# 3_LTE_2.net
KiCad netlist of a schematic drawn in Altium Designer
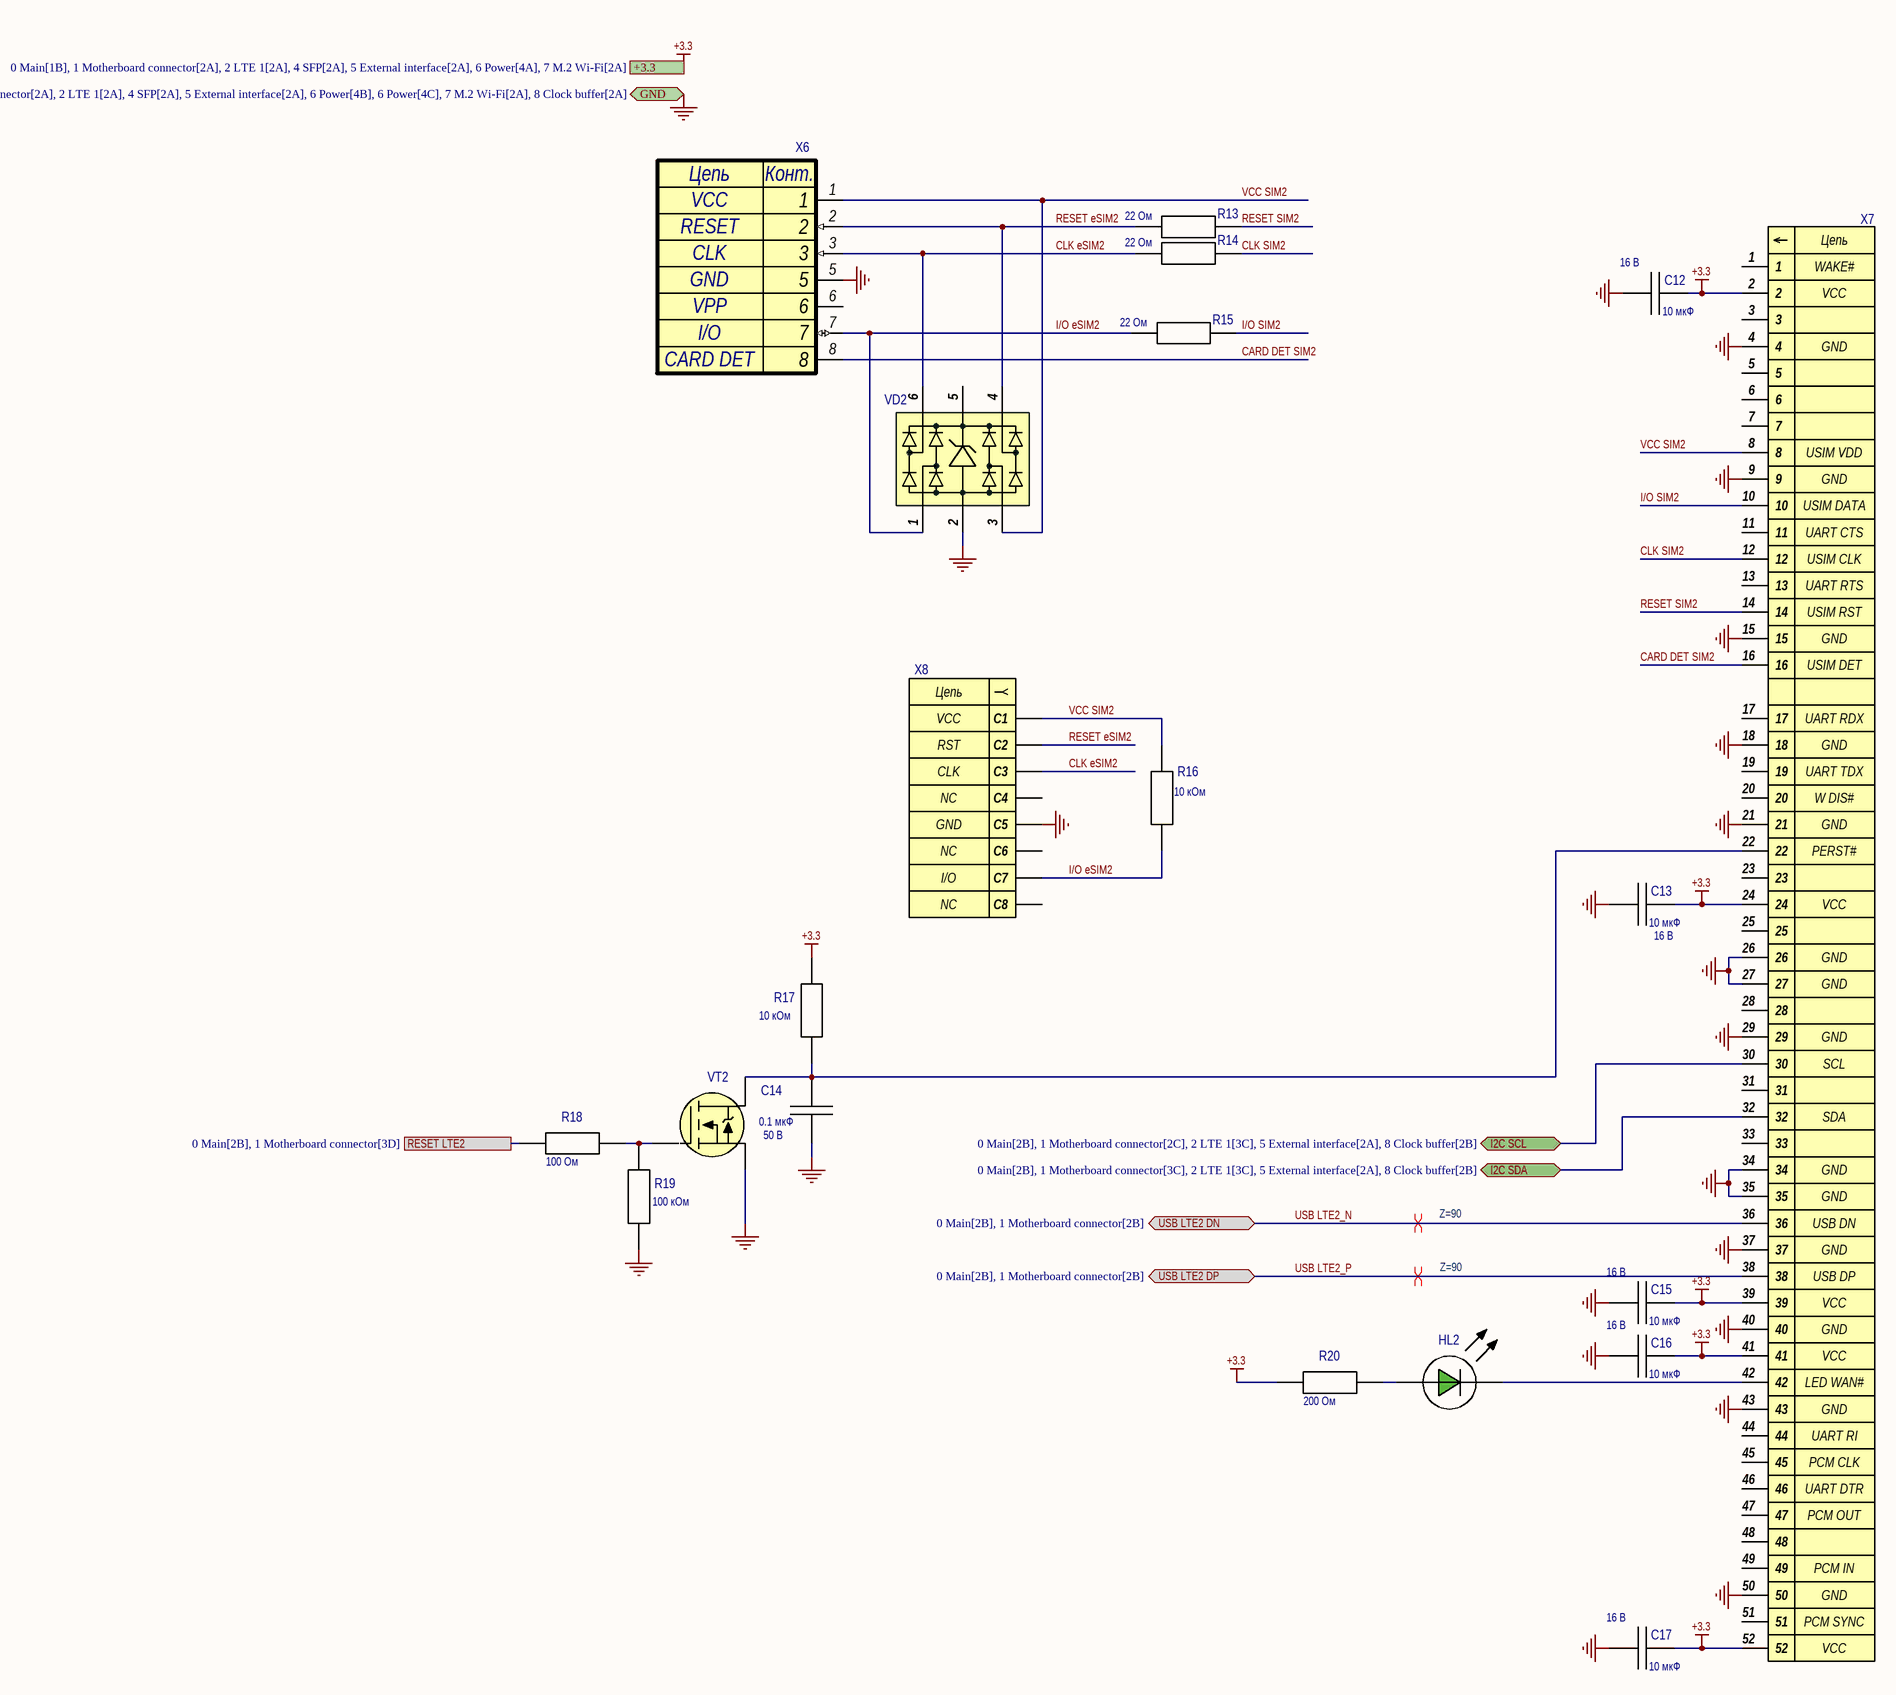
[diagram p0: 3 LTE 2.SchDoc]

(export (version "E")
  (design (tool "Eeschema 10.0.6"))
  (components
    (comp (ref "C12")
      (value "10 мкФ")
      (footprint "CAP_0805")
      (description "Конденсатор CHIP-0805 10 мкФ 16 В 10% X5R")
      (fields
        (field (name "PARTNUMBER") "GRM21BR61C106KE15L")
        (field (name "TOLERANCE") "10%")
        (field (name "НАПРЯЖЕНИЕ") "16 В")
        (field (name "AUTOR") "Цислав А.Н.")
      )
      (libsource (lib "Database_Altium") (part "STD_CAP"))
    )
    (comp (ref "C13")
      (value "10 мкФ")
      (footprint "CAP_0805")
      (description "Конденсатор CHIP-0805 10 мкФ 16 В 10% X5R")
      (fields
        (field (name "PARTNUMBER") "GRM21BR61C106KE15L")
        (field (name "TOLERANCE") "10%")
        (field (name "НАПРЯЖЕНИЕ") "16 В")
        (field (name "AUTOR") "Цислав А.Н.")
      )
      (libsource (lib "Database_Altium") (part "STD_CAP"))
    )
    (comp (ref "C14")
      (value "0.1 мкФ")
      (footprint "CAP_0402")
      (description "Конденсатор CHIP-0402 0.1 мкФ 50 В 10% X7R")
      (fields
        (field (name "PARTNUMBER") "CC0402KRX7R9BB104")
        (field (name "TOLERANCE") "10%")
        (field (name "НАПРЯЖЕНИЕ") "50 В")
        (field (name "AUTOR") "Admin")
      )
      (libsource (lib "Database_Altium") (part "STD_CAP"))
    )
    (comp (ref "C15")
      (value "10 мкФ")
      (footprint "CAP_0805")
      (description "Конденсатор CHIP-0805 10 мкФ 16 В 10% X5R")
      (fields
        (field (name "PARTNUMBER") "GRM21BR61C106KE15L")
        (field (name "TOLERANCE") "10%")
        (field (name "НАПРЯЖЕНИЕ") "16 В")
        (field (name "AUTOR") "Цислав А.Н.")
      )
      (libsource (lib "Database_Altium") (part "STD_CAP"))
    )
    (comp (ref "C16")
      (value "10 мкФ")
      (footprint "CAP_0805")
      (description "Конденсатор CHIP-0805 10 мкФ 16 В 10% X5R")
      (fields
        (field (name "PARTNUMBER") "GRM21BR61C106KE15L")
        (field (name "TOLERANCE") "10%")
        (field (name "НАПРЯЖЕНИЕ") "16 В")
        (field (name "AUTOR") "Цислав А.Н.")
      )
      (libsource (lib "Database_Altium") (part "STD_CAP"))
    )
    (comp (ref "C17")
      (value "10 мкФ")
      (footprint "CAP_0805")
      (description "Конденсатор CHIP-0805 10 мкФ 16 В 10% X5R")
      (fields
        (field (name "PARTNUMBER") "GRM21BR61C106KE15L")
        (field (name "TOLERANCE") "10%")
        (field (name "НАПРЯЖЕНИЕ") "16 В")
        (field (name "AUTOR") "Цислав А.Н.")
      )
      (libsource (lib "Database_Altium") (part "STD_CAP"))
    )
    (comp (ref "HL2")
      (value "APHHS1005CGCK")
      (footprint "LED_0402_GREEN")
      (description "Диод Kingbright 2 В 20 мА")
      (fields (field (name "MANUFACTURER") "Kingbright") (field (name "AUTOR") "Цислав А.Н."))
      (libsource (lib "Database_Altium") (part "APHHS1005CGCK"))
    )
    (comp (ref "R13")
      (value "22 Ом")
      (footprint "RES_0402")
      (description "Резистор CHIP-0402 22 Ом 1%")
      (fields
        (field (name "PARTNUMBER") "RC0402FR-0722RL")
        (field (name "TOLERANCE") "1%")
        (field (name "AUTOR") "Цислав А.Н.")
      )
      (libsource (lib "Database_Altium") (part "STD_RES"))
    )
    (comp (ref "R14")
      (value "22 Ом")
      (footprint "RES_0402")
      (description "Резистор CHIP-0402 22 Ом 1%")
      (fields
        (field (name "PARTNUMBER") "RC0402FR-0722RL")
        (field (name "TOLERANCE") "1%")
        (field (name "AUTOR") "Цислав А.Н.")
      )
      (libsource (lib "Database_Altium") (part "STD_RES"))
    )
    (comp (ref "R15")
      (value "22 Ом")
      (footprint "RES_0402")
      (description "Резистор CHIP-0402 22 Ом 1%")
      (fields
        (field (name "PARTNUMBER") "RC0402FR-0722RL")
        (field (name "TOLERANCE") "1%")
        (field (name "AUTOR") "Цислав А.Н.")
      )
      (libsource (lib "Database_Altium") (part "STD_RES"))
    )
    (comp (ref "R16")
      (value "10 кОм")
      (footprint "RES_0402")
      (description "Резистор CHIP-0402 10 кОм 5%")
      (fields
        (field (name "PARTNUMBER") "RC0402JR-0710KL")
        (field (name "TOLERANCE") "5%")
        (field (name "AUTOR") "Цислав А.Н.")
      )
      (libsource (lib "Database_Altium") (part "STD_RES"))
    )
    (comp (ref "R17")
      (value "10 кОм")
      (footprint "RES_0402")
      (description "Резистор CHIP-0402 10 кОм 5%")
      (fields
        (field (name "PARTNUMBER") "RC0402JR-0710KL")
        (field (name "TOLERANCE") "5%")
        (field (name "AUTOR") "Цислав А.Н.")
      )
      (libsource (lib "Database_Altium") (part "STD_RES"))
    )
    (comp (ref "R18")
      (value "100 Ом")
      (footprint "RES_0402")
      (description "Резистор CHIP-0402 100 Ом 5%")
      (fields
        (field (name "PARTNUMBER") "RC0402JR-07100RL")
        (field (name "TOLERANCE") "5%")
        (field (name "AUTOR") "Цислав А.Н.")
      )
      (libsource (lib "Database_Altium") (part "STD_RES"))
    )
    (comp (ref "R19")
      (value "100 кОм")
      (footprint "RES_0402")
      (description "Резистор CHIP-0402 100 кОм 5%")
      (fields
        (field (name "PARTNUMBER") "RC0402JR-07100KL")
        (field (name "TOLERANCE") "5%")
        (field (name "AUTOR") "Цислав А.Н.")
      )
      (libsource (lib "Database_Altium") (part "STD_RES"))
    )
    (comp (ref "R20")
      (value "200 Ом")
      (footprint "RES_0402")
      (description "Резистор CHIP-0402 200 Ом 5%")
      (fields
        (field (name "PARTNUMBER") "RC0402JR-07200RL")
        (field (name "TOLERANCE") "5%")
        (field (name "AUTOR") "Цислав А.Н.")
      )
      (libsource (lib "Database_Altium") (part "STD_RES"))
    )
    (comp (ref "VD2")
      (value "SRV05-4")
      (footprint "SOT-23-6")
      (description "Диод SEMTECH 1.2 В 12 А")
      (fields (field (name "MANUFACTURER") "SEMTECH") (field (name "AUTOR") "Admin"))
      (libsource (lib "Database_Altium") (part "SRV05-4"))
    )
    (comp (ref "VT2")
      (value "2N7002P")
      (footprint "SOT-23-3")
      (description "Микросхема NXP  N-channel Trench MOSFET")
      (fields
        (field (name "VOLTAGE") "60В")
        (field (name "MANUFACTURER") "NXP")
        (field (name "AUTOR") "Admin")
      )
      (libsource (lib "Database_Altium") (part "2N7002P"))
    )
    (comp (ref "X6")
      (value "Sim холдер с детектированием sim-card  и выдвижным держателем SMN-327-KT1B")
      (footprint "SMN-328-ACP7")
      (description "Разъем XunPu SIM")
      (fields
        (field (name "PARTNUMBER") "SMN-328-ACP7")
        (field (name "MANUFACTURER") "XunPu")
        (field (name "CONTACT") "8")
        (field (name "AUTOR") "Admin")
      )
      (libsource (lib "Database_Altium") (part "Sim WITH CD"))
    )
    (comp (ref "X7")
      (value "2041262-1")
      (footprint "2041262-1")
      (description "Разъем TE PCI-E")
      (fields (field (name "MANUFACTURER") "TE") (field (name "CONTACT") "52") (field (name "AUTOR") "Admin"))
      (libsource (lib "Database_Altium") (part "2041262-1"))
    )
    (comp (ref "X8")
      (value "SIM_MFF2")
      (footprint "SIM_MFF2")
      (description "Разъем E - SIM")
      (fields (field (name "MANUFACTURER") "E -") (field (name "CONTACT") "8") (field (name "AUTOR") "Admin"))
      (libsource (lib "Database_Altium") (part "SIM_MFF2"))
    )
  )
  (nets
    (net (code "1") (name "+3.3") (class "Default")
      (node (ref "C12") (pin "1") (pinfunction "1_1") (pintype "passive"))
      (node (ref "C13") (pin "1") (pinfunction "1_1") (pintype "passive"))
      (node (ref "C15") (pin "1") (pinfunction "1_1") (pintype "passive"))
      (node (ref "C16") (pin "1") (pinfunction "1_1") (pintype "passive"))
      (node (ref "C17") (pin "1") (pinfunction "1_1") (pintype "passive"))
      (node (ref "R17") (pin "2") (pinfunction "2_2") (pintype "passive"))
      (node (ref "R20") (pin "1") (pinfunction "1_1") (pintype "passive"))
      (node (ref "X7") (pin "2") (pinfunction "2_2") (pintype "passive"))
      (node (ref "X7") (pin "24") (pinfunction "24_24") (pintype "passive"))
      (node (ref "X7") (pin "39") (pinfunction "39_39") (pintype "passive"))
      (node (ref "X7") (pin "41") (pinfunction "41_41") (pintype "passive"))
      (node (ref "X7") (pin "52") (pinfunction "52_52") (pintype "passive"))
    )
    (net (code "2") (name "/CARD DET SIM2") (class "Default")
      (node (ref "X6") (pin "8") (pinfunction "8_8") (pintype "power_in"))
      (node (ref "X7") (pin "16") (pinfunction "16_16") (pintype "passive"))
    )
    (net (code "3") (name "/CLK SIM2") (class "Default")
      (node (ref "R14") (pin "2") (pinfunction "2_2") (pintype "passive"))
      (node (ref "X7") (pin "12") (pinfunction "12_12") (pintype "passive"))
    )
    (net (code "4") (name "/CLK eSIM2") (class "Default")
      (node (ref "R14") (pin "1") (pinfunction "1_1") (pintype "passive"))
      (node (ref "VD2") (pin "6") (pinfunction "6_6") (pintype "passive"))
      (node (ref "X6") (pin "3") (pinfunction "3_3") (pintype "input"))
      (node (ref "X8") (pin "C3") (pinfunction "C3_C3") (pintype "passive"))
    )
    (net (code "5") (name "/I2C SCL") (class "Default")
      (node (ref "X7") (pin "30") (pinfunction "30_30") (pintype "passive"))
    )
    (net (code "6") (name "/I2C SDA") (class "Default")
      (node (ref "X7") (pin "32") (pinfunction "32_32") (pintype "passive"))
    )
    (net (code "7") (name "/I{slash}O SIM2") (class "Default")
      (node (ref "R15") (pin "2") (pinfunction "2_2") (pintype "passive"))
      (node (ref "X7") (pin "10") (pinfunction "10_10") (pintype "passive"))
    )
    (net (code "8") (name "/I{slash}O eSIM2") (class "Default")
      (node (ref "R15") (pin "1") (pinfunction "1_1") (pintype "passive"))
      (node (ref "R16") (pin "1") (pinfunction "1_1") (pintype "passive"))
      (node (ref "VD2") (pin "1") (pinfunction "1_1") (pintype "passive"))
      (node (ref "X6") (pin "7") (pinfunction "7_7") (pintype "bidirectional"))
      (node (ref "X8") (pin "C7") (pinfunction "C7_C7") (pintype "passive"))
    )
    (net (code "9") (name "/RESET LTE2") (class "Default")
      (node (ref "R18") (pin "1") (pinfunction "1_1") (pintype "passive"))
    )
    (net (code "10") (name "/RESET SIM2") (class "Default")
      (node (ref "R13") (pin "2") (pinfunction "2_2") (pintype "passive"))
      (node (ref "X7") (pin "14") (pinfunction "14_14") (pintype "passive"))
    )
    (net (code "11") (name "/RESET eSIM2") (class "Default")
      (node (ref "R13") (pin "1") (pinfunction "1_1") (pintype "passive"))
      (node (ref "VD2") (pin "4") (pinfunction "4_4") (pintype "passive"))
      (node (ref "X6") (pin "2") (pinfunction "2_2") (pintype "input"))
      (node (ref "X8") (pin "C2") (pinfunction "C2_C2") (pintype "passive"))
    )
    (net (code "12") (name "/USB LTE2_N") (class "Default")
      (node (ref "X7") (pin "36") (pinfunction "36_36") (pintype "passive"))
    )
    (net (code "13") (name "/USB LTE2_P") (class "Default")
      (node (ref "X7") (pin "38") (pinfunction "38_38") (pintype "passive"))
    )
    (net (code "14") (name "/VCC SIM2") (class "Default")
      (node (ref "R16") (pin "2") (pinfunction "2_2") (pintype "passive"))
      (node (ref "VD2") (pin "3") (pinfunction "3_3") (pintype "passive"))
      (node (ref "X6") (pin "1") (pinfunction "1_1") (pintype "power_in"))
      (node (ref "X7") (pin "8") (pinfunction "8_8") (pintype "passive"))
      (node (ref "X8") (pin "C1") (pinfunction "C1_C1") (pintype "passive"))
    )
    (net (code "15") (name "GND") (class "Default")
      (node (ref "C12") (pin "2") (pinfunction "2_2") (pintype "passive"))
      (node (ref "C13") (pin "2") (pinfunction "2_2") (pintype "passive"))
      (node (ref "C14") (pin "2") (pinfunction "2_2") (pintype "passive"))
      (node (ref "C15") (pin "2") (pinfunction "2_2") (pintype "passive"))
      (node (ref "C16") (pin "2") (pinfunction "2_2") (pintype "passive"))
      (node (ref "C17") (pin "2") (pinfunction "2_2") (pintype "passive"))
      (node (ref "R19") (pin "1") (pinfunction "1_1") (pintype "passive"))
      (node (ref "VD2") (pin "2") (pinfunction "2_2") (pintype "passive"))
      (node (ref "VT2") (pin "2") (pinfunction "S_2") (pintype "passive"))
      (node (ref "X6") (pin "5") (pinfunction "5_5") (pintype "passive"))
      (node (ref "X7") (pin "15") (pinfunction "15_15") (pintype "passive"))
      (node (ref "X7") (pin "18") (pinfunction "18_18") (pintype "passive"))
      (node (ref "X7") (pin "21") (pinfunction "21_21") (pintype "passive"))
      (node (ref "X7") (pin "26") (pinfunction "26_26") (pintype "passive"))
      (node (ref "X7") (pin "27") (pinfunction "27_27") (pintype "passive"))
      (node (ref "X7") (pin "29") (pinfunction "29_29") (pintype "passive"))
      (node (ref "X7") (pin "34") (pinfunction "34_34") (pintype "passive"))
      (node (ref "X7") (pin "35") (pinfunction "35_35") (pintype "passive"))
      (node (ref "X7") (pin "37") (pinfunction "37_37") (pintype "passive"))
      (node (ref "X7") (pin "4") (pinfunction "4_4") (pintype "passive"))
      (node (ref "X7") (pin "40") (pinfunction "40_40") (pintype "passive"))
      (node (ref "X7") (pin "43") (pinfunction "43_43") (pintype "passive"))
      (node (ref "X7") (pin "50") (pinfunction "50_50") (pintype "passive"))
      (node (ref "X7") (pin "9") (pinfunction "9_9") (pintype "passive"))
      (node (ref "X8") (pin "C5") (pinfunction "C5_C5") (pintype "passive"))
    )
    (net (code "16") (name "Net-(HL2-A)") (class "Default")
      (node (ref "HL2") (pin "1") (pinfunction "A_1") (pintype "power_in"))
      (node (ref "R20") (pin "2") (pinfunction "2_2") (pintype "passive"))
    )
    (net (code "17") (name "Net-(HL2-K)") (class "Default")
      (node (ref "HL2") (pin "2") (pinfunction "K_2") (pintype "power_in"))
      (node (ref "X7") (pin "42") (pinfunction "42_42") (pintype "passive"))
    )
    (net (code "18") (name "Net-(VT2-D)") (class "Default")
      (node (ref "C14") (pin "1") (pinfunction "1_1") (pintype "passive"))
      (node (ref "R17") (pin "1") (pinfunction "1_1") (pintype "passive"))
      (node (ref "VT2") (pin "3") (pinfunction "D_3") (pintype "passive"))
      (node (ref "X7") (pin "22") (pinfunction "22_22") (pintype "passive"))
    )
    (net (code "19") (name "Net-(VT2-G)") (class "Default")
      (node (ref "R18") (pin "2") (pinfunction "2_2") (pintype "passive"))
      (node (ref "R19") (pin "2") (pinfunction "2_2") (pintype "passive"))
      (node (ref "VT2") (pin "1") (pinfunction "G_1") (pintype "passive"))
    )
    (net (code "20") (name "unconnected-(VD2-Pad5)") (class "Default")
      (node (ref "VD2") (pin "5") (pinfunction "5_5") (pintype "passive"))
    )
    (net (code "21") (name "unconnected-(X6-Pad6)") (class "Default")
      (node (ref "X6") (pin "6") (pinfunction "6_6") (pintype "power_in"))
    )
    (net (code "22") (name "unconnected-(X7-Pad1)") (class "Default")
      (node (ref "X7") (pin "1") (pinfunction "1_1") (pintype "passive"))
    )
    (net (code "23") (name "unconnected-(X7-Pad3)") (class "Default")
      (node (ref "X7") (pin "3") (pinfunction "3_3") (pintype "passive"))
    )
    (net (code "24") (name "unconnected-(X7-Pad5)") (class "Default")
      (node (ref "X7") (pin "5") (pinfunction "5_5") (pintype "passive"))
    )
    (net (code "25") (name "unconnected-(X7-Pad6)") (class "Default")
      (node (ref "X7") (pin "6") (pinfunction "6_6") (pintype "passive"))
    )
    (net (code "26") (name "unconnected-(X7-Pad7)") (class "Default")
      (node (ref "X7") (pin "7") (pinfunction "7_7") (pintype "passive"))
    )
    (net (code "27") (name "unconnected-(X7-Pad11)") (class "Default")
      (node (ref "X7") (pin "11") (pinfunction "11_11") (pintype "passive"))
    )
    (net (code "28") (name "unconnected-(X7-Pad13)") (class "Default")
      (node (ref "X7") (pin "13") (pinfunction "13_13") (pintype "passive"))
    )
    (net (code "29") (name "unconnected-(X7-Pad17)") (class "Default")
      (node (ref "X7") (pin "17") (pinfunction "17_17") (pintype "passive"))
    )
    (net (code "30") (name "unconnected-(X7-Pad19)") (class "Default")
      (node (ref "X7") (pin "19") (pinfunction "19_19") (pintype "passive"))
    )
    (net (code "31") (name "unconnected-(X7-Pad20)") (class "Default")
      (node (ref "X7") (pin "20") (pinfunction "20_20") (pintype "passive"))
    )
    (net (code "32") (name "unconnected-(X7-Pad23)") (class "Default")
      (node (ref "X7") (pin "23") (pinfunction "23_23") (pintype "passive"))
    )
    (net (code "33") (name "unconnected-(X7-Pad25)") (class "Default")
      (node (ref "X7") (pin "25") (pinfunction "25_25") (pintype "passive"))
    )
    (net (code "34") (name "unconnected-(X7-Pad28)") (class "Default")
      (node (ref "X7") (pin "28") (pinfunction "28_28") (pintype "passive"))
    )
    (net (code "35") (name "unconnected-(X7-Pad31)") (class "Default")
      (node (ref "X7") (pin "31") (pinfunction "31_31") (pintype "passive"))
    )
    (net (code "36") (name "unconnected-(X7-Pad33)") (class "Default")
      (node (ref "X7") (pin "33") (pinfunction "33_33") (pintype "passive"))
    )
    (net (code "37") (name "unconnected-(X7-Pad44)") (class "Default")
      (node (ref "X7") (pin "44") (pinfunction "44_44") (pintype "passive"))
    )
    (net (code "38") (name "unconnected-(X7-Pad45)") (class "Default")
      (node (ref "X7") (pin "45") (pinfunction "45_45") (pintype "passive"))
    )
    (net (code "39") (name "unconnected-(X7-Pad46)") (class "Default")
      (node (ref "X7") (pin "46") (pinfunction "46_46") (pintype "passive"))
    )
    (net (code "40") (name "unconnected-(X7-Pad47)") (class "Default")
      (node (ref "X7") (pin "47") (pinfunction "47_47") (pintype "passive"))
    )
    (net (code "41") (name "unconnected-(X7-Pad48)") (class "Default")
      (node (ref "X7") (pin "48") (pinfunction "48_48") (pintype "passive"))
    )
    (net (code "42") (name "unconnected-(X7-Pad49)") (class "Default")
      (node (ref "X7") (pin "49") (pinfunction "49_49") (pintype "passive"))
    )
    (net (code "43") (name "unconnected-(X7-Pad51)") (class "Default")
      (node (ref "X7") (pin "51") (pinfunction "51_51") (pintype "passive"))
    )
    (net (code "44") (name "unconnected-(X8-PadC4)") (class "Default")
      (node (ref "X8") (pin "C4") (pinfunction "C4_C4") (pintype "passive"))
    )
    (net (code "45") (name "unconnected-(X8-PadC6)") (class "Default")
      (node (ref "X8") (pin "C6") (pinfunction "C6_C6") (pintype "passive"))
    )
    (net (code "46") (name "unconnected-(X8-PadC8)") (class "Default")
      (node (ref "X8") (pin "C8") (pinfunction "C8_C8") (pintype "passive"))
    )
  )
)
